# TwistIt.net
KiCad netlist of a schematic drawn in EAGLE
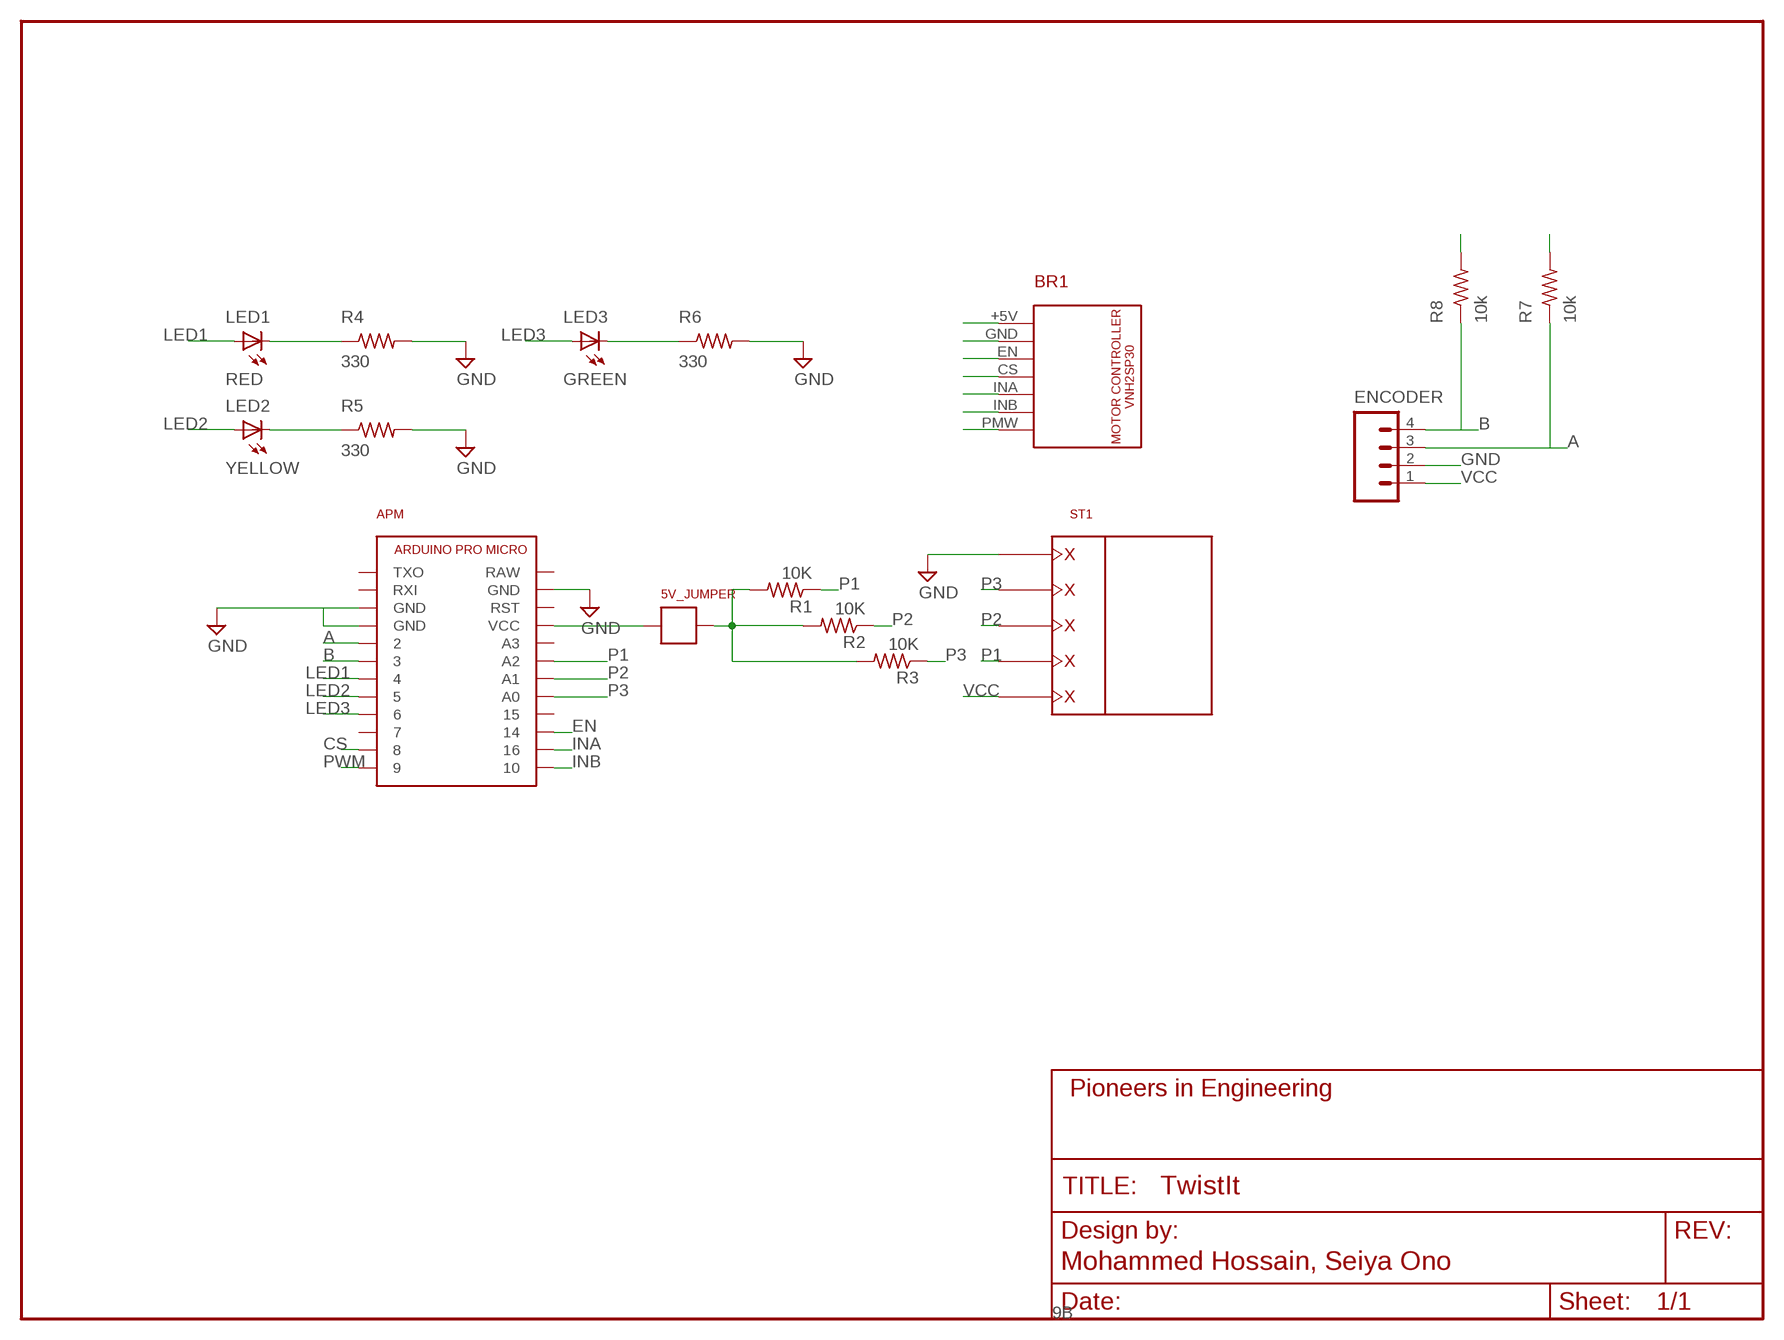
[diagram p0: schematic, sheet 1]

(export (version "E")
  (design (tool "Eeschema 10.0.6"))
  (components
    (comp (ref "5V_JUMPER")
      (value "JUMPER")
      (footprint "eagle-import:JUMPER")
      (fields
        (field (name "DISTRIBUTOR_PART_NUMBER") "952-2262-ND")
        (field (name "MANUFACTURER") "Harwin. Inc")
        (field (name "MANUFACTURER_PART_NUMBER") "M20-9990246")
      )
      (libsource (lib "eagle-import") (part "JUMPER"))
    )
    (comp (ref "APM")
      (value "ARDUINO_PRO_MICRO")
      (footprint "eagle-import:ARDUINO_PRO_MICRO")
      (fields
        (field (name "DISTRIBUTOR_PART_NUMBER") "32284746884")
        (field (name "MANUFACTURER") "Feiyang electronics")
      )
      (libsource (lib "eagle-import") (part "ARDUINO_PRO_MICRO"))
    )
    (comp (ref "BR1")
      (value "VNH2SP30_MOTOR_CONTROLLER")
      (footprint "eagle-import:VNH2SP30_MOTOR_CONTROLLER")
      (libsource (lib "eagle-import") (part "VNH2SP30_MOTOR_CONTROLLER"))
    )
    (comp (ref "ENCODER")
      (value "M041X04-MTA")
      (footprint "eagle-import:1X04-MTA")
      (libsource (lib "eagle-import") (part "M041X04-MTA"))
    )
    (comp (ref "LED1")
      (value "RED")
      (footprint "eagle-import:FKIT-LED-1206")
      (libsource (lib "eagle-import") (part "LED-FKIT-1206"))
    )
    (comp (ref "LED2")
      (value "YELLOW")
      (footprint "eagle-import:FKIT-LED-1206")
      (libsource (lib "eagle-import") (part "LED-FKIT-1206"))
    )
    (comp (ref "LED3")
      (value "GREEN")
      (footprint "eagle-import:FKIT-LED-1206")
      (libsource (lib "eagle-import") (part "LED-FKIT-1206"))
    )
    (comp (ref "R1")
      (value "10K")
      (footprint "eagle-import:R0603")
      (libsource (lib "eagle-import") (part "resistor_R-US_R0603"))
    )
    (comp (ref "R2")
      (value "10K")
      (footprint "eagle-import:R0603")
      (libsource (lib "eagle-import") (part "resistor_R-US_R0603"))
    )
    (comp (ref "R3")
      (value "10K")
      (footprint "eagle-import:R0603")
      (libsource (lib "eagle-import") (part "resistor_R-US_R0603"))
    )
    (comp (ref "R4")
      (value "330")
      (footprint "eagle-import:R0603")
      (fields (field (name "MANUFACTURER") "Rohm Semiconductor"))
      (libsource (lib "eagle-import") (part "R-US_R0603"))
    )
    (comp (ref "R5")
      (value "330")
      (footprint "eagle-import:R0603")
      (fields (field (name "MANUFACTURER") "Rohm Semiconductor"))
      (libsource (lib "eagle-import") (part "R-US_R0603"))
    )
    (comp (ref "R6")
      (value "330")
      (footprint "eagle-import:R0603")
      (fields (field (name "MANUFACTURER") "Rohm Semiconductor"))
      (libsource (lib "eagle-import") (part "R-US_R0603"))
    )
    (comp (ref "R7")
      (value "10k")
      (footprint "eagle-import:R0603")
      (fields (field (name "MANUFACTURER") "Rohm Semiconductor"))
      (libsource (lib "eagle-import") (part "R-US_R0603"))
    )
    (comp (ref "R8")
      (value "10k")
      (footprint "eagle-import:R0603")
      (fields (field (name "MANUFACTURER") "Rohm Semiconductor"))
      (libsource (lib "eagle-import") (part "R-US_R0603"))
    )
    (comp (ref "ST1")
      (value "5PIN_SCREW")
      (footprint "eagle-import:5PIN_SCREW")
      (fields
        (field (name "DISTRIBUTOR_PART_NUMBER") "277-1239-ND")
        (field (name "MANUFACTURER") "Phoenix Contact")
        (field (name "MANUFACTURER_PART_NUMBER") "1729047")
      )
      (libsource (lib "eagle-import") (part "5PIN_SCREW"))
    )
  )
  (nets
    (net (code "1") (name "/A") (class "Default")
      (node (ref "APM") (pin "2") (pinfunction "2_2") (pintype "bidirectional"))
      (node (ref "ENCODER") (pin "3") (pinfunction "3_3") (pintype "passive"))
      (node (ref "R7") (pin "1") (pinfunction "1_1") (pintype "passive"))
    )
    (net (code "2") (name "/B") (class "Default")
      (node (ref "APM") (pin "3") (pinfunction "3_3") (pintype "bidirectional"))
      (node (ref "ENCODER") (pin "4") (pinfunction "4_4") (pintype "passive"))
      (node (ref "R8") (pin "1") (pinfunction "1_1") (pintype "passive"))
    )
    (net (code "3") (name "/CS") (class "Default")
      (node (ref "APM") (pin "8") (pinfunction "8_8") (pintype "bidirectional"))
      (node (ref "BR1") (pin "CS") (pinfunction "CS_CS") (pintype "bidirectional"))
    )
    (net (code "4") (name "/EN") (class "Default")
      (node (ref "APM") (pin "14") (pinfunction "14_14") (pintype "bidirectional"))
      (node (ref "BR1") (pin "EN") (pinfunction "EN_EN") (pintype "bidirectional"))
    )
    (net (code "5") (name "/INA") (class "Default")
      (node (ref "APM") (pin "16") (pinfunction "16_16") (pintype "bidirectional"))
      (node (ref "BR1") (pin "INA") (pinfunction "INA_INA") (pintype "bidirectional"))
    )
    (net (code "6") (name "/INB") (class "Default")
      (node (ref "APM") (pin "10") (pinfunction "10_10") (pintype "bidirectional"))
      (node (ref "BR1") (pin "INB") (pinfunction "INB_INB") (pintype "bidirectional"))
    )
    (net (code "7") (name "/LED1") (class "Default")
      (node (ref "APM") (pin "4") (pinfunction "4_4") (pintype "bidirectional"))
      (node (ref "LED1") (pin "A") (pinfunction "A_A") (pintype "passive"))
    )
    (net (code "8") (name "/LED2") (class "Default")
      (node (ref "APM") (pin "5") (pinfunction "5_5") (pintype "bidirectional"))
      (node (ref "LED2") (pin "A") (pinfunction "A_A") (pintype "passive"))
    )
    (net (code "9") (name "/LED3") (class "Default")
      (node (ref "APM") (pin "6") (pinfunction "6_6") (pintype "bidirectional"))
      (node (ref "LED3") (pin "A") (pinfunction "A_A") (pintype "passive"))
    )
    (net (code "10") (name "/P1") (class "Default")
      (node (ref "APM") (pin "A2") (pinfunction "A2_A2") (pintype "bidirectional"))
      (node (ref "R1") (pin "1") (pinfunction "1_1") (pintype "passive"))
      (node (ref "ST1") (pin "P$4") (pinfunction "P$4_P$4") (pintype "bidirectional"))
    )
    (net (code "11") (name "/P2") (class "Default")
      (node (ref "APM") (pin "A1") (pinfunction "A1_A1") (pintype "bidirectional"))
      (node (ref "R2") (pin "1") (pinfunction "1_1") (pintype "passive"))
      (node (ref "ST1") (pin "P$3") (pinfunction "P$3_P$3") (pintype "bidirectional"))
    )
    (net (code "12") (name "/P3") (class "Default")
      (node (ref "APM") (pin "A0") (pinfunction "A0_A0") (pintype "bidirectional"))
      (node (ref "R3") (pin "1") (pinfunction "1_1") (pintype "passive"))
      (node (ref "ST1") (pin "P$2") (pinfunction "P$2_P$2") (pintype "bidirectional"))
    )
    (net (code "13") (name "/PWM") (class "Default")
      (node (ref "APM") (pin "9") (pinfunction "9_9") (pintype "bidirectional"))
      (node (ref "BR1") (pin "PMW") (pinfunction "PMW_PMW") (pintype "bidirectional"))
    )
    (net (code "14") (name "/VCC") (class "Default")
      (node (ref "5V_JUMPER") (pin "P$1") (pinfunction "P$1_P$1") (pintype "input"))
      (node (ref "APM") (pin "VCC") (pinfunction "VCC_VCC") (pintype "bidirectional"))
      (node (ref "BR1") (pin "+5V") (pinfunction "+5V_+5V") (pintype "bidirectional"))
      (node (ref "ENCODER") (pin "1") (pinfunction "1_1") (pintype "passive"))
      (node (ref "R7") (pin "2") (pinfunction "2_2") (pintype "passive"))
      (node (ref "R8") (pin "2") (pinfunction "2_2") (pintype "passive"))
      (node (ref "ST1") (pin "P$5") (pinfunction "P$5_P$5") (pintype "bidirectional"))
    )
    (net (code "15") (name "GND") (class "Default")
      (node (ref "APM") (pin "GND@0") (pinfunction "GND_GND@0") (pintype "bidirectional"))
      (node (ref "APM") (pin "GND@1") (pinfunction "GND_GND@1") (pintype "bidirectional"))
      (node (ref "APM") (pin "GND@2") (pinfunction "GND_GND@2") (pintype "bidirectional"))
      (node (ref "BR1") (pin "GND") (pinfunction "GND_GND") (pintype "bidirectional"))
      (node (ref "ENCODER") (pin "2") (pinfunction "2_2") (pintype "passive"))
      (node (ref "R4") (pin "2") (pinfunction "2_2") (pintype "passive"))
      (node (ref "R5") (pin "2") (pinfunction "2_2") (pintype "passive"))
      (node (ref "R6") (pin "2") (pinfunction "2_2") (pintype "passive"))
      (node (ref "ST1") (pin "P$1") (pinfunction "P$1_P$1") (pintype "bidirectional"))
    )
    (net (code "16") (name "Net-(5V_JUMPER-PadP$2)") (class "Default")
      (node (ref "5V_JUMPER") (pin "P$2") (pinfunction "P$2_P$2") (pintype "bidirectional"))
      (node (ref "R1") (pin "2") (pinfunction "2_2") (pintype "passive"))
      (node (ref "R2") (pin "2") (pinfunction "2_2") (pintype "passive"))
      (node (ref "R3") (pin "2") (pinfunction "2_2") (pintype "passive"))
    )
    (net (code "17") (name "Net-(LED1-PadC)") (class "Default")
      (node (ref "LED1") (pin "C") (pinfunction "C_C") (pintype "passive"))
      (node (ref "R4") (pin "1") (pinfunction "1_1") (pintype "passive"))
    )
    (net (code "18") (name "Net-(LED2-PadC)") (class "Default")
      (node (ref "LED2") (pin "C") (pinfunction "C_C") (pintype "passive"))
      (node (ref "R5") (pin "1") (pinfunction "1_1") (pintype "passive"))
    )
    (net (code "19") (name "Net-(LED3-PadC)") (class "Default")
      (node (ref "LED3") (pin "C") (pinfunction "C_C") (pintype "passive"))
      (node (ref "R6") (pin "1") (pinfunction "1_1") (pintype "passive"))
    )
    (net (code "20") (name "unconnected-(APM-Pad7)") (class "Default")
      (node (ref "APM") (pin "7") (pinfunction "7_7") (pintype "bidirectional"))
    )
    (net (code "21") (name "unconnected-(APM-Pad15)") (class "Default")
      (node (ref "APM") (pin "15") (pinfunction "15_15") (pintype "bidirectional"))
    )
    (net (code "22") (name "unconnected-(APM-PadA3)") (class "Default")
      (node (ref "APM") (pin "A3") (pinfunction "A3_A3") (pintype "bidirectional"))
    )
    (net (code "23") (name "unconnected-(APM-PadRAW)") (class "Default")
      (node (ref "APM") (pin "RAW") (pinfunction "RAW_RAW") (pintype "bidirectional"))
    )
    (net (code "24") (name "unconnected-(APM-PadRST)") (class "Default")
      (node (ref "APM") (pin "RST") (pinfunction "RST_RST") (pintype "bidirectional"))
    )
    (net (code "25") (name "unconnected-(APM-PadRXI)") (class "Default")
      (node (ref "APM") (pin "RXI") (pinfunction "RXI_RXI") (pintype "bidirectional"))
    )
    (net (code "26") (name "unconnected-(APM-PadTXO)") (class "Default")
      (node (ref "APM") (pin "TXO") (pinfunction "TXO_TXO") (pintype "bidirectional"))
    )
  )
)
